# mokkamaster.net
KiCad netlist of a schematic drawn in EAGLE
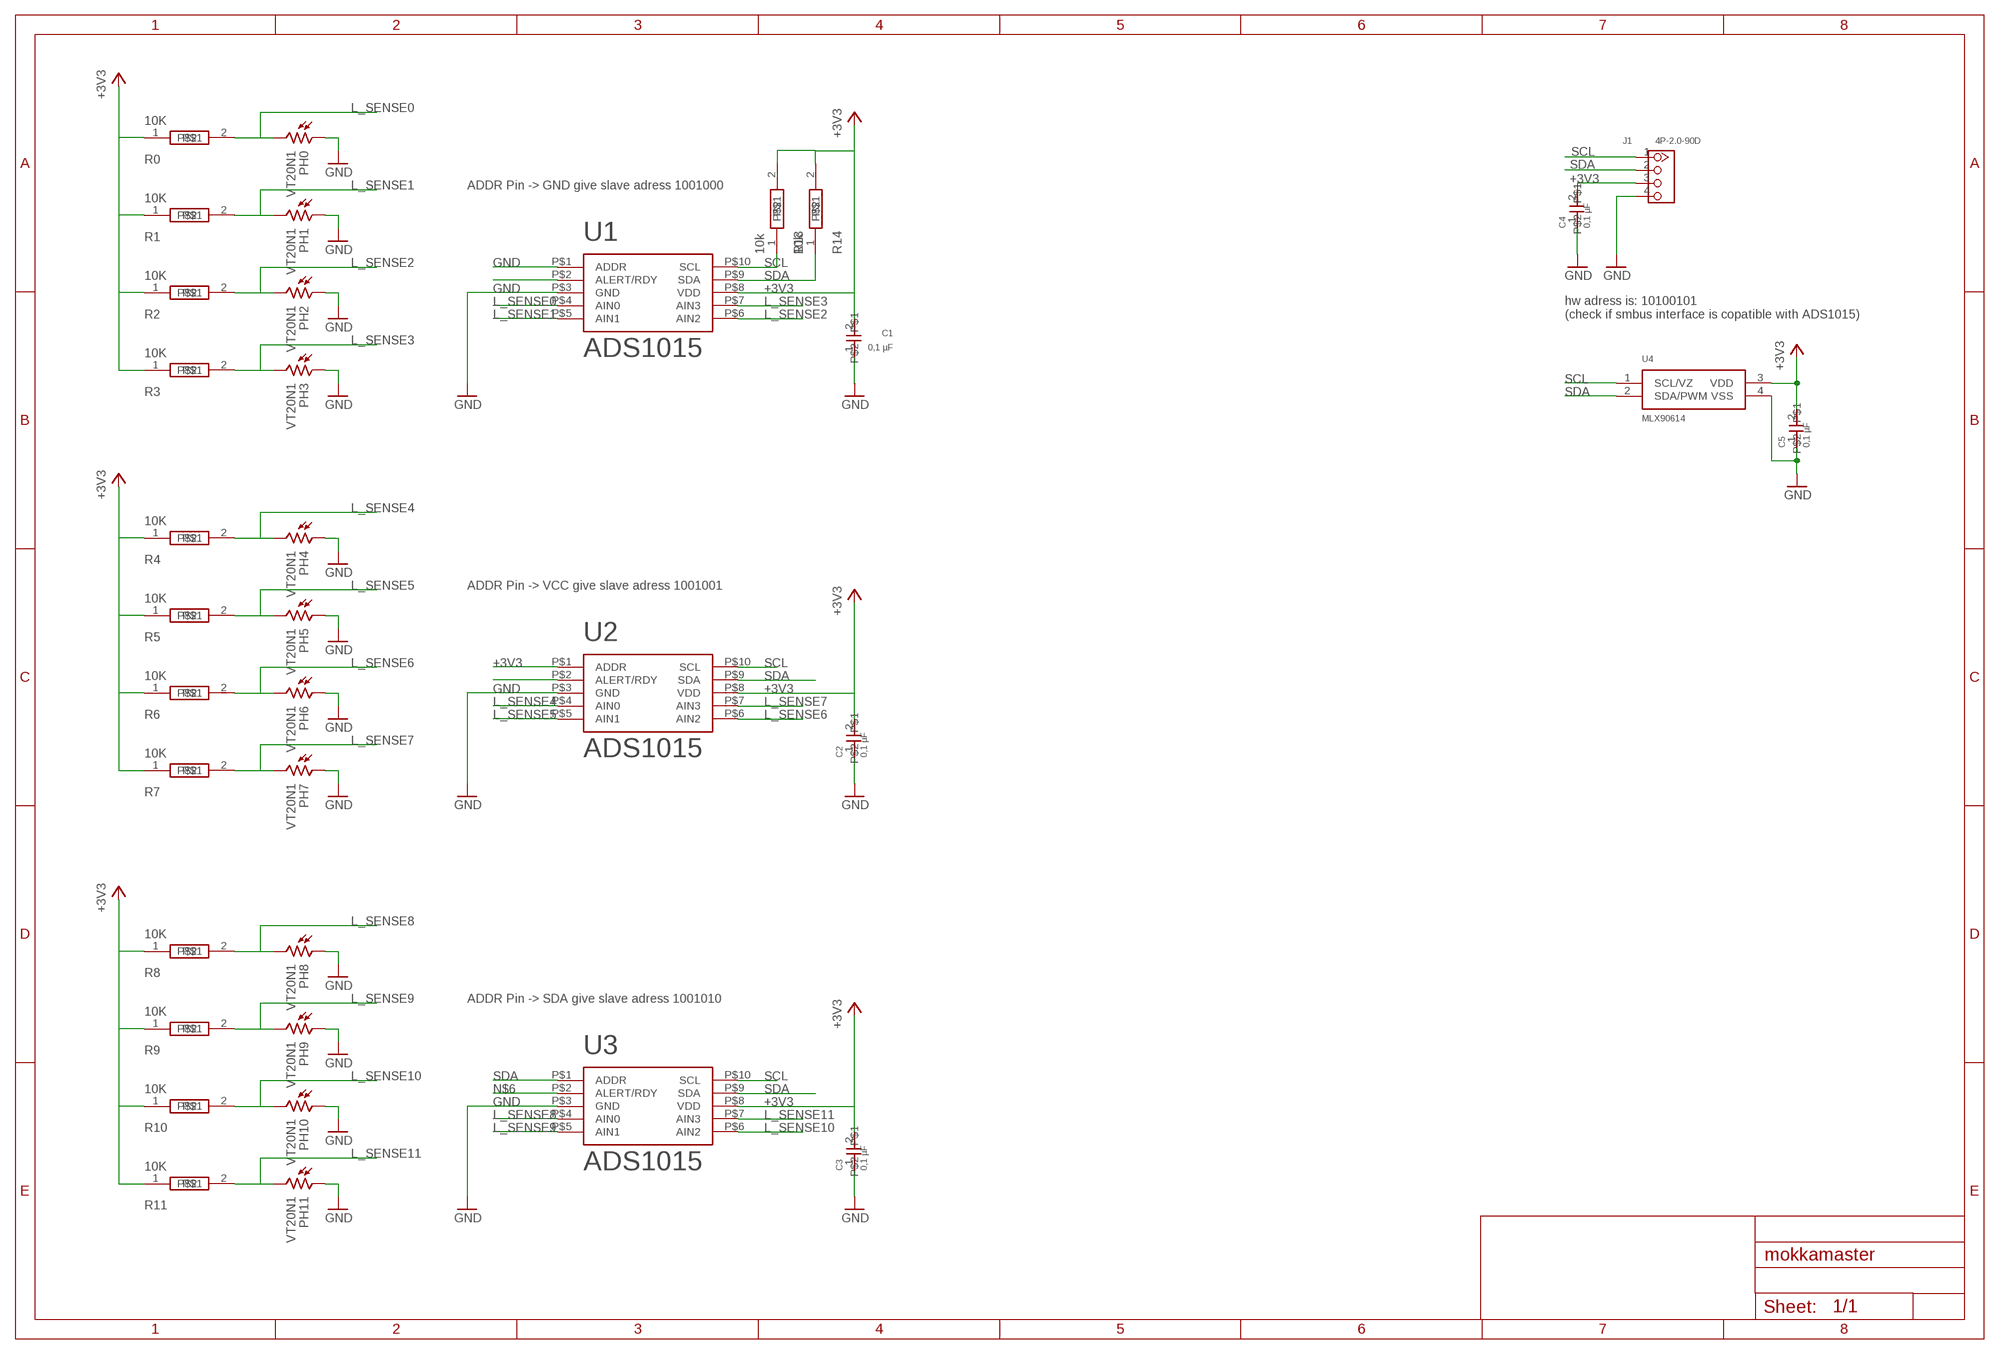
[diagram p0: schematic, sheet 1]

(export (version "E")
  (design (tool "Eeschema 10.0.6"))
  (components
    (comp (ref "C1")
      (value "0,1 µF")
      (footprint "eagle-import:C0603")
      (libsource (lib "eagle-import") (part "CAPACITOR_GENERIC"))
    )
    (comp (ref "C2")
      (value "0,1 µF")
      (footprint "eagle-import:C0603")
      (libsource (lib "eagle-import") (part "CAPACITOR_GENERIC"))
    )
    (comp (ref "C3")
      (value "0,1 µF")
      (footprint "eagle-import:C0603")
      (libsource (lib "eagle-import") (part "CAPACITOR_GENERIC"))
    )
    (comp (ref "C4")
      (value "0,1 µF")
      (footprint "eagle-import:C0603")
      (libsource (lib "eagle-import") (part "CAPACITOR_GENERIC"))
    )
    (comp (ref "C5")
      (value "0,1 µF")
      (footprint "eagle-import:C0603")
      (libsource (lib "eagle-import") (part "CAPACITOR_GENERIC"))
    )
    (comp (ref "J1")
      (value "4P-2.0-90D")
      (footprint "eagle-import:HW4-2.0-90D")
      (fields (field (name "SPICEPREFIX") "X"))
      (libsource (lib "eagle-import") (part "GROVE-CONNECTOR-DIP-90D(4P-2.0)"))
    )
    (comp (ref "PH0")
      (value "VT20N1")
      (footprint "eagle-import:TO46-VT200")
      (libsource (lib "eagle-import") (part "VT20N1"))
    )
    (comp (ref "PH1")
      (value "VT20N1")
      (footprint "eagle-import:TO46-VT200")
      (libsource (lib "eagle-import") (part "VT20N1"))
    )
    (comp (ref "PH2")
      (value "VT20N1")
      (footprint "eagle-import:TO46-VT200")
      (libsource (lib "eagle-import") (part "VT20N1"))
    )
    (comp (ref "PH3")
      (value "VT20N1")
      (footprint "eagle-import:TO46-VT200")
      (libsource (lib "eagle-import") (part "VT20N1"))
    )
    (comp (ref "PH4")
      (value "VT20N1")
      (footprint "eagle-import:TO46-VT200")
      (libsource (lib "eagle-import") (part "VT20N1"))
    )
    (comp (ref "PH5")
      (value "VT20N1")
      (footprint "eagle-import:TO46-VT200")
      (libsource (lib "eagle-import") (part "VT20N1"))
    )
    (comp (ref "PH6")
      (value "VT20N1")
      (footprint "eagle-import:TO46-VT200")
      (libsource (lib "eagle-import") (part "VT20N1"))
    )
    (comp (ref "PH7")
      (value "VT20N1")
      (footprint "eagle-import:TO46-VT200")
      (libsource (lib "eagle-import") (part "VT20N1"))
    )
    (comp (ref "PH8")
      (value "VT20N1")
      (footprint "eagle-import:TO46-VT200")
      (libsource (lib "eagle-import") (part "VT20N1"))
    )
    (comp (ref "PH9")
      (value "VT20N1")
      (footprint "eagle-import:TO46-VT200")
      (libsource (lib "eagle-import") (part "VT20N1"))
    )
    (comp (ref "PH10")
      (value "VT20N1")
      (footprint "eagle-import:TO46-VT200")
      (libsource (lib "eagle-import") (part "VT20N1"))
    )
    (comp (ref "PH11")
      (value "VT20N1")
      (footprint "eagle-import:TO46-VT200")
      (libsource (lib "eagle-import") (part "VT20N1"))
    )
    (comp (ref "R0")
      (value "10K")
      (footprint "eagle-import:R0603")
      (libsource (lib "eagle-import") (part "RESISTOR_GENERIC"))
    )
    (comp (ref "R1")
      (value "10K")
      (footprint "eagle-import:R0603")
      (libsource (lib "eagle-import") (part "RESISTOR_GENERIC"))
    )
    (comp (ref "R2")
      (value "10K")
      (footprint "eagle-import:R0603")
      (libsource (lib "eagle-import") (part "RESISTOR_GENERIC"))
    )
    (comp (ref "R3")
      (value "10K")
      (footprint "eagle-import:R0603")
      (libsource (lib "eagle-import") (part "RESISTOR_GENERIC"))
    )
    (comp (ref "R4")
      (value "10K")
      (footprint "eagle-import:R0603")
      (libsource (lib "eagle-import") (part "RESISTOR_GENERIC"))
    )
    (comp (ref "R5")
      (value "10K")
      (footprint "eagle-import:R0603")
      (libsource (lib "eagle-import") (part "RESISTOR_GENERIC"))
    )
    (comp (ref "R6")
      (value "10K")
      (footprint "eagle-import:R0603")
      (libsource (lib "eagle-import") (part "RESISTOR_GENERIC"))
    )
    (comp (ref "R7")
      (value "10K")
      (footprint "eagle-import:R0603")
      (libsource (lib "eagle-import") (part "RESISTOR_GENERIC"))
    )
    (comp (ref "R8")
      (value "10K")
      (footprint "eagle-import:R0603")
      (libsource (lib "eagle-import") (part "RESISTOR_GENERIC"))
    )
    (comp (ref "R9")
      (value "10K")
      (footprint "eagle-import:R0603")
      (libsource (lib "eagle-import") (part "RESISTOR_GENERIC"))
    )
    (comp (ref "R10")
      (value "10K")
      (footprint "eagle-import:R0603")
      (libsource (lib "eagle-import") (part "RESISTOR_GENERIC"))
    )
    (comp (ref "R11")
      (value "10K")
      (footprint "eagle-import:R0603")
      (libsource (lib "eagle-import") (part "RESISTOR_GENERIC"))
    )
    (comp (ref "R13")
      (value "10k")
      (footprint "eagle-import:R0603")
      (libsource (lib "eagle-import") (part "RESISTOR_GENERIC"))
    )
    (comp (ref "R14")
      (value "10k")
      (footprint "eagle-import:R0603")
      (libsource (lib "eagle-import") (part "RESISTOR_GENERIC"))
    )
    (comp (ref "U1")
      (value "ADS1015")
      (footprint "eagle-import:PDSO-G10")
      (libsource (lib "eagle-import") (part "ADS1015"))
    )
    (comp (ref "U2")
      (value "ADS1015")
      (footprint "eagle-import:PDSO-G10")
      (libsource (lib "eagle-import") (part "ADS1015"))
    )
    (comp (ref "U3")
      (value "ADS1015")
      (footprint "eagle-import:PDSO-G10")
      (libsource (lib "eagle-import") (part "ADS1015"))
    )
    (comp (ref "U4")
      (value "MLX90614")
      (footprint "eagle-import:SPARKFUN_TO-39")
      (libsource (lib "eagle-import") (part "MLX90614"))
    )
  )
  (nets
    (net (code "1") (name "+3V3") (class "Default")
      (node (ref "C1") (pin "2") (pinfunction "P$2_2") (pintype "bidirectional"))
      (node (ref "C2") (pin "2") (pinfunction "P$2_2") (pintype "bidirectional"))
      (node (ref "C3") (pin "2") (pinfunction "P$2_2") (pintype "bidirectional"))
      (node (ref "C4") (pin "2") (pinfunction "P$2_2") (pintype "bidirectional"))
      (node (ref "C5") (pin "2") (pinfunction "P$2_2") (pintype "bidirectional"))
      (node (ref "J1") (pin "3") (pinfunction "3_3") (pintype "bidirectional"))
      (node (ref "R0") (pin "1") (pinfunction "P$1_1") (pintype "bidirectional"))
      (node (ref "R1") (pin "1") (pinfunction "P$1_1") (pintype "bidirectional"))
      (node (ref "R10") (pin "1") (pinfunction "P$1_1") (pintype "bidirectional"))
      (node (ref "R11") (pin "1") (pinfunction "P$1_1") (pintype "bidirectional"))
      (node (ref "R13") (pin "2") (pinfunction "P$2_2") (pintype "bidirectional"))
      (node (ref "R14") (pin "2") (pinfunction "P$2_2") (pintype "bidirectional"))
      (node (ref "R2") (pin "1") (pinfunction "P$1_1") (pintype "bidirectional"))
      (node (ref "R3") (pin "1") (pinfunction "P$1_1") (pintype "bidirectional"))
      (node (ref "R4") (pin "1") (pinfunction "P$1_1") (pintype "bidirectional"))
      (node (ref "R5") (pin "1") (pinfunction "P$1_1") (pintype "bidirectional"))
      (node (ref "R6") (pin "1") (pinfunction "P$1_1") (pintype "bidirectional"))
      (node (ref "R7") (pin "1") (pinfunction "P$1_1") (pintype "bidirectional"))
      (node (ref "R8") (pin "1") (pinfunction "P$1_1") (pintype "bidirectional"))
      (node (ref "R9") (pin "1") (pinfunction "P$1_1") (pintype "bidirectional"))
      (node (ref "U1") (pin "P$8") (pinfunction "VDD_P$8") (pintype "bidirectional"))
      (node (ref "U2") (pin "P$1") (pinfunction "ADDR_P$1") (pintype "bidirectional"))
      (node (ref "U2") (pin "P$8") (pinfunction "VDD_P$8") (pintype "bidirectional"))
      (node (ref "U3") (pin "P$8") (pinfunction "VDD_P$8") (pintype "bidirectional"))
      (node (ref "U4") (pin "3") (pinfunction "VDD_3") (pintype "power_in"))
    )
    (net (code "2") (name "/L_SENSE0") (class "Default")
      (node (ref "PH0") (pin "2") (pinfunction "2_2") (pintype "passive"))
      (node (ref "R0") (pin "2") (pinfunction "P$2_2") (pintype "bidirectional"))
      (node (ref "U1") (pin "P$4") (pinfunction "AIN0_P$4") (pintype "bidirectional"))
    )
    (net (code "3") (name "/L_SENSE1") (class "Default")
      (node (ref "PH1") (pin "2") (pinfunction "2_2") (pintype "passive"))
      (node (ref "R1") (pin "2") (pinfunction "P$2_2") (pintype "bidirectional"))
      (node (ref "U1") (pin "P$5") (pinfunction "AIN1_P$5") (pintype "bidirectional"))
    )
    (net (code "4") (name "/L_SENSE2") (class "Default")
      (node (ref "PH2") (pin "2") (pinfunction "2_2") (pintype "passive"))
      (node (ref "R2") (pin "2") (pinfunction "P$2_2") (pintype "bidirectional"))
      (node (ref "U1") (pin "P$6") (pinfunction "AIN2_P$6") (pintype "bidirectional"))
    )
    (net (code "5") (name "/L_SENSE3") (class "Default")
      (node (ref "PH3") (pin "2") (pinfunction "2_2") (pintype "passive"))
      (node (ref "R3") (pin "2") (pinfunction "P$2_2") (pintype "bidirectional"))
      (node (ref "U1") (pin "P$7") (pinfunction "AIN3_P$7") (pintype "bidirectional"))
    )
    (net (code "6") (name "/L_SENSE4") (class "Default")
      (node (ref "PH4") (pin "2") (pinfunction "2_2") (pintype "passive"))
      (node (ref "R4") (pin "2") (pinfunction "P$2_2") (pintype "bidirectional"))
      (node (ref "U2") (pin "P$4") (pinfunction "AIN0_P$4") (pintype "bidirectional"))
    )
    (net (code "7") (name "/L_SENSE5") (class "Default")
      (node (ref "PH5") (pin "2") (pinfunction "2_2") (pintype "passive"))
      (node (ref "R5") (pin "2") (pinfunction "P$2_2") (pintype "bidirectional"))
      (node (ref "U2") (pin "P$5") (pinfunction "AIN1_P$5") (pintype "bidirectional"))
    )
    (net (code "8") (name "/L_SENSE6") (class "Default")
      (node (ref "PH6") (pin "2") (pinfunction "2_2") (pintype "passive"))
      (node (ref "R6") (pin "2") (pinfunction "P$2_2") (pintype "bidirectional"))
      (node (ref "U2") (pin "P$6") (pinfunction "AIN2_P$6") (pintype "bidirectional"))
    )
    (net (code "9") (name "/L_SENSE7") (class "Default")
      (node (ref "PH7") (pin "2") (pinfunction "2_2") (pintype "passive"))
      (node (ref "R7") (pin "2") (pinfunction "P$2_2") (pintype "bidirectional"))
      (node (ref "U2") (pin "P$7") (pinfunction "AIN3_P$7") (pintype "bidirectional"))
    )
    (net (code "10") (name "/L_SENSE8") (class "Default")
      (node (ref "PH8") (pin "2") (pinfunction "2_2") (pintype "passive"))
      (node (ref "R8") (pin "2") (pinfunction "P$2_2") (pintype "bidirectional"))
      (node (ref "U3") (pin "P$4") (pinfunction "AIN0_P$4") (pintype "bidirectional"))
    )
    (net (code "11") (name "/L_SENSE9") (class "Default")
      (node (ref "PH9") (pin "2") (pinfunction "2_2") (pintype "passive"))
      (node (ref "R9") (pin "2") (pinfunction "P$2_2") (pintype "bidirectional"))
      (node (ref "U3") (pin "P$5") (pinfunction "AIN1_P$5") (pintype "bidirectional"))
    )
    (net (code "12") (name "/L_SENSE10") (class "Default")
      (node (ref "PH10") (pin "2") (pinfunction "2_2") (pintype "passive"))
      (node (ref "R10") (pin "2") (pinfunction "P$2_2") (pintype "bidirectional"))
      (node (ref "U3") (pin "P$6") (pinfunction "AIN2_P$6") (pintype "bidirectional"))
    )
    (net (code "13") (name "/L_SENSE11") (class "Default")
      (node (ref "PH11") (pin "2") (pinfunction "2_2") (pintype "passive"))
      (node (ref "R11") (pin "2") (pinfunction "P$2_2") (pintype "bidirectional"))
      (node (ref "U3") (pin "P$7") (pinfunction "AIN3_P$7") (pintype "bidirectional"))
    )
    (net (code "14") (name "/N$6") (class "Default")
      (node (ref "U3") (pin "P$2") (pinfunction "ALERT/RDY_P$2") (pintype "bidirectional"))
    )
    (net (code "15") (name "/SCL") (class "Default")
      (node (ref "J1") (pin "1") (pinfunction "1_1") (pintype "bidirectional"))
      (node (ref "R13") (pin "1") (pinfunction "P$1_1") (pintype "bidirectional"))
      (node (ref "U1") (pin "P$10") (pinfunction "SCL_P$10") (pintype "bidirectional"))
      (node (ref "U2") (pin "P$10") (pinfunction "SCL_P$10") (pintype "bidirectional"))
      (node (ref "U3") (pin "P$10") (pinfunction "SCL_P$10") (pintype "bidirectional"))
      (node (ref "U4") (pin "1") (pinfunction "SCL/VZ_1") (pintype "bidirectional"))
    )
    (net (code "16") (name "/SDA") (class "Default")
      (node (ref "J1") (pin "2") (pinfunction "2_2") (pintype "bidirectional"))
      (node (ref "R14") (pin "1") (pinfunction "P$1_1") (pintype "bidirectional"))
      (node (ref "U1") (pin "P$9") (pinfunction "SDA_P$9") (pintype "bidirectional"))
      (node (ref "U2") (pin "P$9") (pinfunction "SDA_P$9") (pintype "bidirectional"))
      (node (ref "U3") (pin "P$1") (pinfunction "ADDR_P$1") (pintype "bidirectional"))
      (node (ref "U3") (pin "P$9") (pinfunction "SDA_P$9") (pintype "bidirectional"))
      (node (ref "U4") (pin "2") (pinfunction "SDA/PWM_2") (pintype "bidirectional"))
    )
    (net (code "17") (name "GND") (class "Default")
      (node (ref "C1") (pin "1") (pinfunction "P$1_1") (pintype "bidirectional"))
      (node (ref "C2") (pin "1") (pinfunction "P$1_1") (pintype "bidirectional"))
      (node (ref "C3") (pin "1") (pinfunction "P$1_1") (pintype "bidirectional"))
      (node (ref "C4") (pin "1") (pinfunction "P$1_1") (pintype "bidirectional"))
      (node (ref "C5") (pin "1") (pinfunction "P$1_1") (pintype "bidirectional"))
      (node (ref "J1") (pin "4") (pinfunction "4_4") (pintype "bidirectional"))
      (node (ref "PH0") (pin "1") (pinfunction "1_1") (pintype "passive"))
      (node (ref "PH1") (pin "1") (pinfunction "1_1") (pintype "passive"))
      (node (ref "PH10") (pin "1") (pinfunction "1_1") (pintype "passive"))
      (node (ref "PH11") (pin "1") (pinfunction "1_1") (pintype "passive"))
      (node (ref "PH2") (pin "1") (pinfunction "1_1") (pintype "passive"))
      (node (ref "PH3") (pin "1") (pinfunction "1_1") (pintype "passive"))
      (node (ref "PH4") (pin "1") (pinfunction "1_1") (pintype "passive"))
      (node (ref "PH5") (pin "1") (pinfunction "1_1") (pintype "passive"))
      (node (ref "PH6") (pin "1") (pinfunction "1_1") (pintype "passive"))
      (node (ref "PH7") (pin "1") (pinfunction "1_1") (pintype "passive"))
      (node (ref "PH8") (pin "1") (pinfunction "1_1") (pintype "passive"))
      (node (ref "PH9") (pin "1") (pinfunction "1_1") (pintype "passive"))
      (node (ref "U1") (pin "P$1") (pinfunction "ADDR_P$1") (pintype "bidirectional"))
      (node (ref "U1") (pin "P$3") (pinfunction "GND_P$3") (pintype "bidirectional"))
      (node (ref "U2") (pin "P$3") (pinfunction "GND_P$3") (pintype "bidirectional"))
      (node (ref "U3") (pin "P$3") (pinfunction "GND_P$3") (pintype "bidirectional"))
      (node (ref "U4") (pin "4") (pinfunction "VSS_4") (pintype "power_in"))
    )
    (net (code "18") (name "unconnected-(U1-ALERT{slash}RDY-PadP$2)") (class "Default")
      (node (ref "U1") (pin "P$2") (pinfunction "ALERT/RDY_P$2") (pintype "bidirectional"))
    )
    (net (code "19") (name "unconnected-(U2-ALERT{slash}RDY-PadP$2)") (class "Default")
      (node (ref "U2") (pin "P$2") (pinfunction "ALERT/RDY_P$2") (pintype "bidirectional"))
    )
  )
)
